# RMP_SLIDER_MODULE.net
KiCad netlist of a schematic drawn in Altium Designer
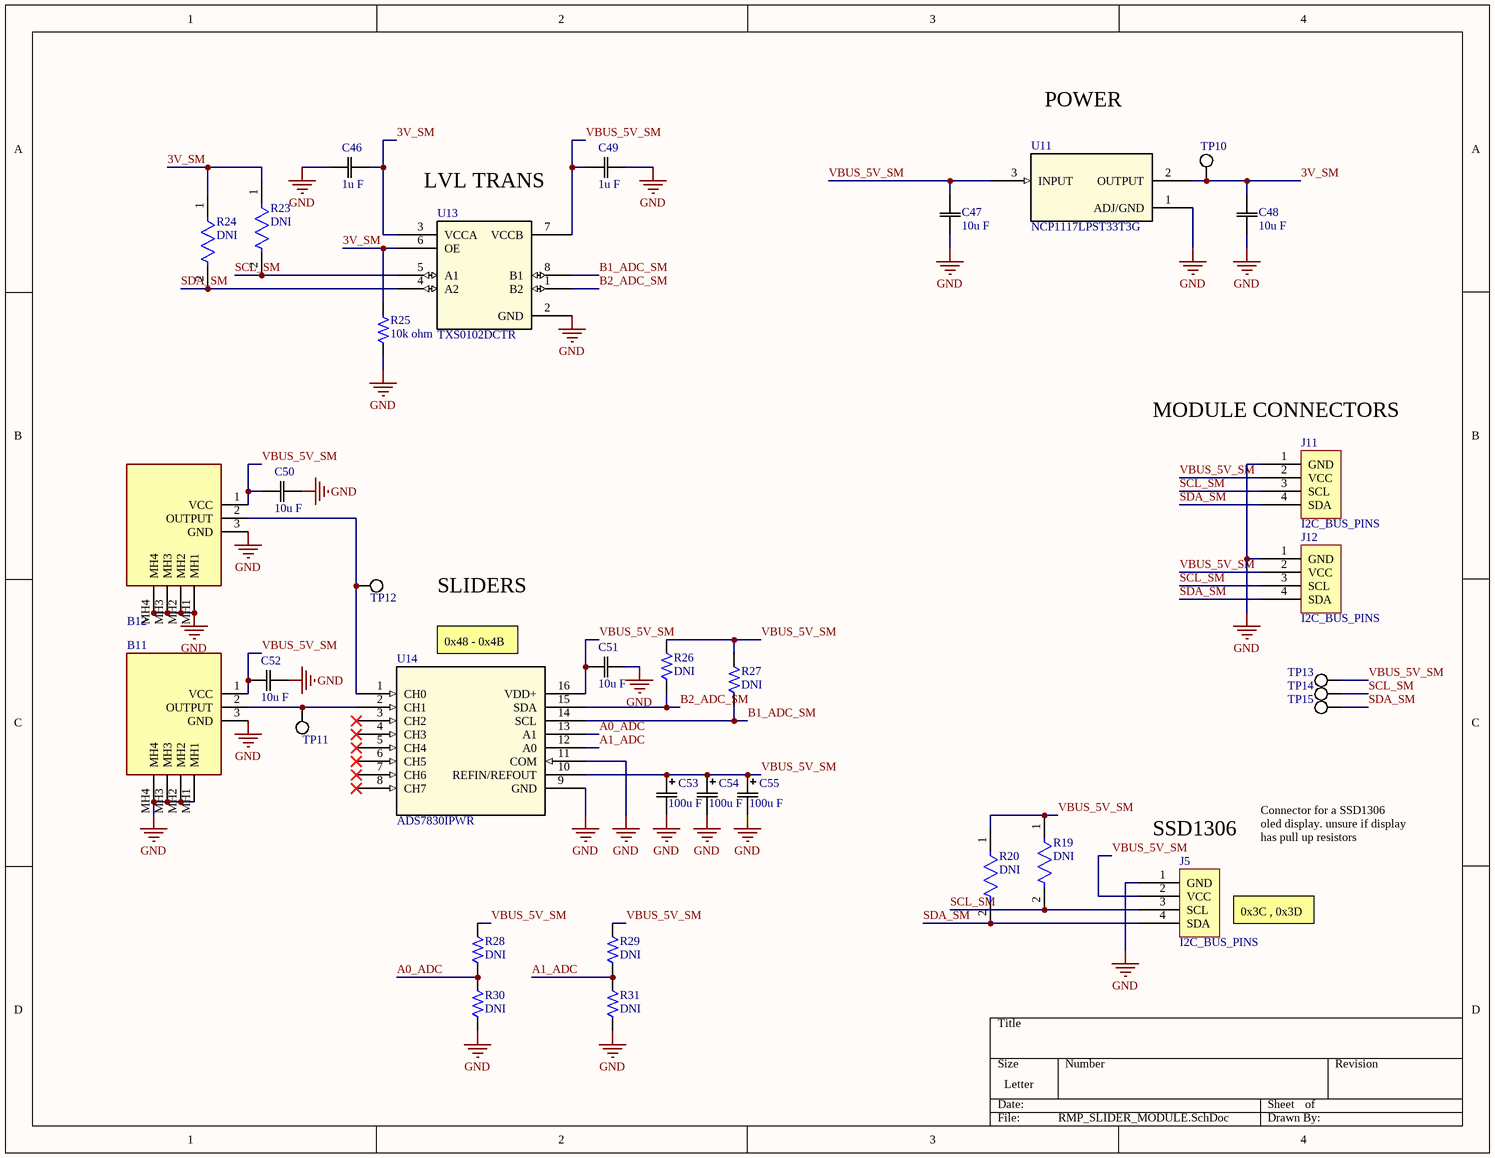
[diagram p0: RMP_SLIDER_MODULE.SchDoc]

(export (version "E")
  (design (tool "Eeschema 10.0.6"))
  (components
    (comp (ref "B11")
      (value "PTA3043-2010CIB103")
      (footprint "PTA30432010CIB103")
      (description "10 kOhms 0.2W, 1/5W Through Hole Slide Potentiometer Top Adjustment Type")
      (fields (field (name "MOUSER PART NUMBER") "652-PTA3432010CIB103"))
      (libsource (lib "Schlib1") (part "PTA3043-2010CIB103"))
    )
    (comp (ref "B12")
      (value "PTA3043-2010CIB103")
      (footprint "PTA30432010CIB103")
      (description "10 kOhms 0.2W, 1/5W Through Hole Slide Potentiometer Top Adjustment Type")
      (fields (field (name "MOUSER PART NUMBER") "652-PTA3432010CIB103"))
      (libsource (lib "Schlib1") (part "PTA3043-2010CIB103"))
    )
    (comp (ref "C46")
      (value "1u F")
      (footprint "CAP_CL21B105KAFNNNE_SAM-M")
      (description "1 µF ±10% 25V Ceramic Capacitor X7R 0805 (2012 Metric)")
      (fields (field (name "Comment") "CL21B105KAFNNNE"))
      (libsource (lib "Schlib1") (part "CAP_CL21B105KAFNNNE"))
    )
    (comp (ref "C47")
      (value "10u F")
      (footprint "G-21_MUR-M")
      (description "10 µF ±10% 16V Ceramic Capacitor X5R 0805 (2012 Metric)")
      (fields (field (name "Comment") "GRM21BR61C106KE15K"))
      (libsource (lib "Schlib1") (part "CAP_GRM21BR61C106KE15K"))
    )
    (comp (ref "C48")
      (value "10u F")
      (footprint "G-21_MUR-M")
      (description "10 µF ±10% 16V Ceramic Capacitor X5R 0805 (2012 Metric)")
      (fields (field (name "Comment") "GRM21BR61C106KE15K"))
      (libsource (lib "Schlib1") (part "CAP_GRM21BR61C106KE15K"))
    )
    (comp (ref "C49")
      (value "1u F")
      (footprint "CAP_CL21B105KAFNNNE_SAM-M")
      (description "1 µF ±10% 25V Ceramic Capacitor X7R 0805 (2012 Metric)")
      (fields (field (name "Comment") "CL21B105KAFNNNE"))
      (libsource (lib "Schlib1") (part "CAP_CL21B105KAFNNNE"))
    )
    (comp (ref "C50")
      (value "10u F")
      (footprint "G-21_MUR-M")
      (description "10 µF ±10% 16V Ceramic Capacitor X5R 0805 (2012 Metric)")
      (fields (field (name "Comment") "GRM21BR61C106KE15K"))
      (libsource (lib "Schlib1") (part "CAP_GRM21BR61C106KE15K"))
    )
    (comp (ref "C51")
      (value "10u F")
      (footprint "G-21_MUR-M")
      (description "10 µF ±10% 16V Ceramic Capacitor X5R 0805 (2012 Metric)")
      (fields (field (name "Comment") "GRM21BR61C106KE15K"))
      (libsource (lib "Schlib1") (part "CAP_GRM21BR61C106KE15K"))
    )
    (comp (ref "C52")
      (value "10u F")
      (footprint "G-21_MUR-M")
      (description "10 µF ±10% 16V Ceramic Capacitor X5R 0805 (2012 Metric)")
      (fields (field (name "Comment") "GRM21BR61C106KE15K"))
      (libsource (lib "Schlib1") (part "CAP_GRM21BR61C106KE15K"))
    )
    (comp (ref "C53")
      (value "100u F")
      (footprint "CAP_YX_6P3X11_RUB")
      (description "CAP ALUM 100UF 20% 35V RADIAL TH")
      (fields (field (name "Comment") "35YXJ100M6.3X11"))
      (libsource (lib "Schlib1") (part "CAP_35YXJ100M6.3X11"))
    )
    (comp (ref "C54")
      (value "100u F")
      (footprint "CAP_YX_6P3X11_RUB")
      (description "CAP ALUM 100UF 20% 35V RADIAL TH")
      (fields (field (name "Comment") "35YXJ100M6.3X11"))
      (libsource (lib "Schlib1") (part "CAP_35YXJ100M6.3X11"))
    )
    (comp (ref "C55")
      (value "100u F")
      (footprint "CAP_YX_6P3X11_RUB")
      (description "CAP ALUM 100UF 20% 35V RADIAL TH")
      (fields (field (name "Comment") "35YXJ100M6.3X11"))
      (libsource (lib "Schlib1") (part "CAP_35YXJ100M6.3X11"))
    )
    (comp (ref "J5")
      (value "I2C_BUS_PINS")
      (footprint "4 PIN HEADER")
      (libsource (lib "Schlib1") (part "I2C_BUS_PINS"))
    )
    (comp (ref "J11")
      (value "I2C_BUS_PINS")
      (footprint "4 PIN HEADER")
      (libsource (lib "Schlib1") (part "I2C_BUS_PINS"))
    )
    (comp (ref "J12")
      (value "I2C_BUS_PINS")
      (footprint "4 PIN HEADER")
      (libsource (lib "Schlib1") (part "I2C_BUS_PINS"))
    )
    (comp (ref "R19")
      (value "RT0805FRE134K7L")
      (footprint "FP-RT0805-MFG")
      (description "RT0805 4.7KΩ 0.125W 50 ppm/°C 0.01%")
      (fields
        (field (name "RESISTANCE") "DNI")
        (field (name "TOLERANCE") "0.0001")
        (field (name "MANUFACTURER") "Yageo")
      )
      (libsource (lib "Altium Content Vault") (part "1029c3af85768c4190bb7ad29bc67b5"))
    )
    (comp (ref "R20")
      (value "RT0805FRE134K7L")
      (footprint "FP-RT0805-MFG")
      (description "RT0805 4.7KΩ 0.125W 50 ppm/°C 0.01%")
      (fields
        (field (name "RESISTANCE") "DNI")
        (field (name "TOLERANCE") "0.0001")
        (field (name "MANUFACTURER") "Yageo")
      )
      (libsource (lib "Altium Content Vault") (part "1029c3af85768c4190bb7ad29bc67b5"))
    )
    (comp (ref "R23")
      (value "RT0805FRE134K7L")
      (footprint "FP-RT0805-MFG")
      (description "RT0805 4.7KΩ 0.125W 50 ppm/°C 0.01%")
      (fields
        (field (name "RESISTANCE") "DNI")
        (field (name "TOLERANCE") "0.0001")
        (field (name "MANUFACTURER") "Yageo")
      )
      (libsource (lib "Altium Content Vault") (part "1029c3af85768c4190bb7ad29bc67b5"))
    )
    (comp (ref "R24")
      (value "RT0805FRE134K7L")
      (footprint "FP-RT0805-MFG")
      (description "RT0805 4.7KΩ 0.125W 50 ppm/°C 0.01%")
      (fields
        (field (name "RESISTANCE") "DNI")
        (field (name "TOLERANCE") "0.0001")
        (field (name "MANUFACTURER") "Yageo")
      )
      (libsource (lib "Altium Content Vault") (part "1029c3af85768c4190bb7ad29bc67b5"))
    )
    (comp (ref "R25")
      (value "10k ohm")
      (footprint "STA_RNCP0805_STP-M")
      (description "10 kOhms ±1% 0.25W, 1/4W Chip Resistor 0805 (2012 Metric) Anti-Sulfur Thin Film")
      (fields (field (name "Comment") "RNCP0805FTD10K0"))
      (libsource (lib "Schlib1") (part "RES_RNCP0805FTD10K0"))
    )
    (comp (ref "R26")
      (value "DNI")
      (footprint "STA_RNCP0805_STP-M")
      (description "10 kOhms ±1% 0.25W, 1/4W Chip Resistor 0805 (2012 Metric) Anti-Sulfur Thin Film")
      (fields (field (name "Comment") "RNCP0805FTD10K0"))
      (libsource (lib "Schlib1") (part "RES_RNCP0805FTD10K0"))
    )
    (comp (ref "R27")
      (value "DNI")
      (footprint "STA_RNCP0805_STP-M")
      (description "10 kOhms ±1% 0.25W, 1/4W Chip Resistor 0805 (2012 Metric) Anti-Sulfur Thin Film")
      (fields (field (name "Comment") "RNCP0805FTD10K0"))
      (libsource (lib "Schlib1") (part "RES_RNCP0805FTD10K0"))
    )
    (comp (ref "R28")
      (value "DNI")
      (footprint "STA_RNCP0805_STP-M")
      (description "10 kOhms ±1% 0.25W, 1/4W Chip Resistor 0805 (2012 Metric) Anti-Sulfur Thin Film")
      (fields (field (name "Comment") "RNCP0805FTD10K0"))
      (libsource (lib "Schlib1") (part "RES_RNCP0805FTD10K0"))
    )
    (comp (ref "R29")
      (value "DNI")
      (footprint "STA_RNCP0805_STP-M")
      (description "10 kOhms ±1% 0.25W, 1/4W Chip Resistor 0805 (2012 Metric) Anti-Sulfur Thin Film")
      (fields (field (name "Comment") "RNCP0805FTD10K0"))
      (libsource (lib "Schlib1") (part "RES_RNCP0805FTD10K0"))
    )
    (comp (ref "R30")
      (value "DNI")
      (footprint "STA_RNCP0805_STP-M")
      (description "10 kOhms ±1% 0.25W, 1/4W Chip Resistor 0805 (2012 Metric) Anti-Sulfur Thin Film")
      (fields (field (name "Comment") "RNCP0805FTD10K0"))
      (libsource (lib "Schlib1") (part "RES_RNCP0805FTD10K0"))
    )
    (comp (ref "R31")
      (value "DNI")
      (footprint "STA_RNCP0805_STP-M")
      (description "10 kOhms ±1% 0.25W, 1/4W Chip Resistor 0805 (2012 Metric) Anti-Sulfur Thin Film")
      (fields (field (name "Comment") "RNCP0805FTD10K0"))
      (libsource (lib "Schlib1") (part "RES_RNCP0805FTD10K0"))
    )
    (comp (ref "TP10")
      (value "TestPoint")
      (footprint "Testpoint")
      (libsource (lib "Schlib1") (part "TestPoint"))
    )
    (comp (ref "TP11")
      (value "TestPoint")
      (footprint "Testpoint")
      (libsource (lib "Schlib1") (part "TestPoint"))
    )
    (comp (ref "TP12") (value "TestPoint") (footprint "Testpoint") (libsource (lib "") (part "TestPoint_1")))
    (comp (ref "TP13")
      (value "TestPoint")
      (footprint "Testpoint")
      (libsource (lib "Schlib1") (part "TestPoint"))
    )
    (comp (ref "TP14")
      (value "TestPoint")
      (footprint "Testpoint")
      (libsource (lib "Schlib1") (part "TestPoint"))
    )
    (comp (ref "TP15")
      (value "TestPoint")
      (footprint "Testpoint")
      (libsource (lib "Schlib1") (part "TestPoint"))
    )
    (comp (ref "U11")
      (value "NCP1117LPST33T3G")
      (footprint "SOT223-3_ONS-M")
      (description "Linear Voltage Regulator IC Positive Fixed 1 Output 1A SOT-223")
      (libsource (lib "Schlib1") (part "NCP1117LPST33T3G"))
    )
    (comp (ref "U13")
      (value "TXS0102DCTR")
      (footprint "DCT8")
      (description "Voltage Level Translator Bidirectional 1 Circuit 2 Channel 24Mbps SM8")
      (libsource (lib "Schlib1") (part "TXS0102DCTR"))
    )
    (comp (ref "U14")
      (value "ADS7830IPWR")
      (footprint "PW16-M")
      (description "8 Bit Analog to Digital Converter 4, 8 Input 1 SAR 16-TSSOP")
      (libsource (lib "Schlib1") (part "ADS7830IPWR"))
    )
  )
  (nets
    (net (code "1") (name "/3V_SM") (class "Default")
      (node (ref "C46") (pin "1") (pinfunction "1_1") (pintype "passive"))
      (node (ref "C48") (pin "2") (pinfunction "2_2") (pintype "passive"))
      (node (ref "R23") (pin "1") (pinfunction "1_1") (pintype "passive"))
      (node (ref "R24") (pin "1") (pinfunction "1_1") (pintype "passive"))
      (node (ref "R25") (pin "1") (pinfunction "1_1") (pintype "passive"))
      (node (ref "TP10") (pin "1") (pinfunction "1_1") (pintype "passive"))
      (node (ref "U11") (pin "2") (pinfunction "OUTPUT_2") (pintype "power_in"))
      (node (ref "U13") (pin "3") (pinfunction "VCCA_3") (pintype "power_in"))
      (node (ref "U13") (pin "6") (pinfunction "OE_6") (pintype "power_in"))
    )
    (net (code "2") (name "/A0_ADC") (class "Default")
      (node (ref "R28") (pin "1") (pinfunction "1_1") (pintype "passive"))
      (node (ref "R30") (pin "2") (pinfunction "2_2") (pintype "passive"))
      (node (ref "U14") (pin "13") (pinfunction "A1_13") (pintype "passive"))
    )
    (net (code "3") (name "/A1_ADC") (class "Default")
      (node (ref "R29") (pin "1") (pinfunction "1_1") (pintype "passive"))
      (node (ref "R31") (pin "2") (pinfunction "2_2") (pintype "passive"))
      (node (ref "U14") (pin "12") (pinfunction "A0_12") (pintype "passive"))
    )
    (net (code "4") (name "/B1_ADC_SM") (class "Default")
      (node (ref "R27") (pin "1") (pinfunction "1_1") (pintype "passive"))
      (node (ref "U13") (pin "8") (pinfunction "B1_8") (pintype "bidirectional"))
      (node (ref "U14") (pin "14") (pinfunction "SCL_14") (pintype "passive"))
    )
    (net (code "5") (name "/B2_ADC_SM") (class "Default")
      (node (ref "R26") (pin "1") (pinfunction "1_1") (pintype "passive"))
      (node (ref "U13") (pin "1") (pinfunction "B2_1") (pintype "bidirectional"))
      (node (ref "U14") (pin "15") (pinfunction "SDA_15") (pintype "passive"))
    )
    (net (code "6") (name "/SCL_SM") (class "Default")
      (node (ref "J11") (pin "3") (pinfunction "SCL_3") (pintype "passive"))
      (node (ref "J12") (pin "3") (pinfunction "SCL_3") (pintype "passive"))
      (node (ref "J5") (pin "3") (pinfunction "SCL_3") (pintype "passive"))
      (node (ref "R19") (pin "2") (pinfunction "2_2") (pintype "passive"))
      (node (ref "R23") (pin "2") (pinfunction "2_2") (pintype "passive"))
      (node (ref "TP14") (pin "1") (pinfunction "1_1") (pintype "passive"))
      (node (ref "U13") (pin "5") (pinfunction "A1_5") (pintype "bidirectional"))
    )
    (net (code "7") (name "/SDA_SM") (class "Default")
      (node (ref "J11") (pin "4") (pinfunction "SDA_4") (pintype "passive"))
      (node (ref "J12") (pin "4") (pinfunction "SDA_4") (pintype "passive"))
      (node (ref "J5") (pin "4") (pinfunction "SDA_4") (pintype "passive"))
      (node (ref "R20") (pin "2") (pinfunction "2_2") (pintype "passive"))
      (node (ref "R24") (pin "2") (pinfunction "2_2") (pintype "passive"))
      (node (ref "TP15") (pin "1") (pinfunction "1_1") (pintype "passive"))
      (node (ref "U13") (pin "4") (pinfunction "A2_4") (pintype "bidirectional"))
    )
    (net (code "8") (name "/VBUS_5V_SM") (class "Default")
      (node (ref "B11") (pin "1") (pinfunction "VCC_1") (pintype "passive"))
      (node (ref "B12") (pin "1") (pinfunction "VCC_1") (pintype "passive"))
      (node (ref "C47") (pin "2") (pinfunction "2_2") (pintype "passive"))
      (node (ref "C49") (pin "2") (pinfunction "2_2") (pintype "passive"))
      (node (ref "C50") (pin "2") (pinfunction "2_2") (pintype "passive"))
      (node (ref "C51") (pin "2") (pinfunction "2_2") (pintype "passive"))
      (node (ref "C52") (pin "1") (pinfunction "1_1") (pintype "passive"))
      (node (ref "C53") (pin "1") (pinfunction "1_1") (pintype "passive"))
      (node (ref "C54") (pin "1") (pinfunction "1_1") (pintype "passive"))
      (node (ref "C55") (pin "1") (pinfunction "1_1") (pintype "passive"))
      (node (ref "J11") (pin "2") (pinfunction "VCC_2") (pintype "passive"))
      (node (ref "J12") (pin "2") (pinfunction "VCC_2") (pintype "passive"))
      (node (ref "J5") (pin "2") (pinfunction "VCC_2") (pintype "passive"))
      (node (ref "R19") (pin "1") (pinfunction "1_1") (pintype "passive"))
      (node (ref "R20") (pin "1") (pinfunction "1_1") (pintype "passive"))
      (node (ref "R26") (pin "2") (pinfunction "2_2") (pintype "passive"))
      (node (ref "R27") (pin "2") (pinfunction "2_2") (pintype "passive"))
      (node (ref "R28") (pin "2") (pinfunction "2_2") (pintype "passive"))
      (node (ref "R29") (pin "2") (pinfunction "2_2") (pintype "passive"))
      (node (ref "TP13") (pin "1") (pinfunction "1_1") (pintype "passive"))
      (node (ref "U11") (pin "3") (pinfunction "INPUT_3") (pintype "input"))
      (node (ref "U13") (pin "7") (pinfunction "VCCB_7") (pintype "power_in"))
      (node (ref "U14") (pin "10") (pinfunction "REFIN/REFOUT_10") (pintype "power_in"))
      (node (ref "U14") (pin "16") (pinfunction "VDD+_16") (pintype "power_in"))
    )
    (net (code "9") (name "GND") (class "Default")
      (node (ref "B11") (pin "3") (pinfunction "GND_3") (pintype "passive"))
      (node (ref "B11") (pin "MH1") (pinfunction "MH1_MH1") (pintype "passive"))
      (node (ref "B11") (pin "MH2") (pinfunction "MH2_MH2") (pintype "passive"))
      (node (ref "B11") (pin "MH3") (pinfunction "MH3_MH3") (pintype "passive"))
      (node (ref "B11") (pin "MH4") (pinfunction "MH4_MH4") (pintype "passive"))
      (node (ref "B12") (pin "3") (pinfunction "GND_3") (pintype "passive"))
      (node (ref "B12") (pin "MH1") (pinfunction "MH1_MH1") (pintype "passive"))
      (node (ref "B12") (pin "MH2") (pinfunction "MH2_MH2") (pintype "passive"))
      (node (ref "B12") (pin "MH3") (pinfunction "MH3_MH3") (pintype "passive"))
      (node (ref "B12") (pin "MH4") (pinfunction "MH4_MH4") (pintype "passive"))
      (node (ref "C46") (pin "2") (pinfunction "2_2") (pintype "passive"))
      (node (ref "C47") (pin "1") (pinfunction "1_1") (pintype "passive"))
      (node (ref "C48") (pin "1") (pinfunction "1_1") (pintype "passive"))
      (node (ref "C49") (pin "1") (pinfunction "1_1") (pintype "passive"))
      (node (ref "C50") (pin "1") (pinfunction "1_1") (pintype "passive"))
      (node (ref "C51") (pin "1") (pinfunction "1_1") (pintype "passive"))
      (node (ref "C52") (pin "2") (pinfunction "2_2") (pintype "passive"))
      (node (ref "C53") (pin "2") (pinfunction "2_2") (pintype "passive"))
      (node (ref "C54") (pin "2") (pinfunction "2_2") (pintype "passive"))
      (node (ref "C55") (pin "2") (pinfunction "2_2") (pintype "passive"))
      (node (ref "J11") (pin "1") (pinfunction "GND_1") (pintype "passive"))
      (node (ref "J12") (pin "1") (pinfunction "GND_1") (pintype "passive"))
      (node (ref "J5") (pin "1") (pinfunction "GND_1") (pintype "passive"))
      (node (ref "R25") (pin "2") (pinfunction "2_2") (pintype "passive"))
      (node (ref "R30") (pin "1") (pinfunction "1_1") (pintype "passive"))
      (node (ref "R31") (pin "1") (pinfunction "1_1") (pintype "passive"))
      (node (ref "U11") (pin "1") (pinfunction "ADJ/GND_1") (pintype "power_in"))
      (node (ref "U13") (pin "2") (pinfunction "GND_2") (pintype "power_in"))
      (node (ref "U14") (pin "11") (pinfunction "COM_11") (pintype "input"))
      (node (ref "U14") (pin "9") (pinfunction "GND_9") (pintype "power_in"))
    )
    (net (code "10") (name "Net-(B11-OUTPUT)") (class "Default")
      (node (ref "B11") (pin "2") (pinfunction "OUTPUT_2") (pintype "passive"))
      (node (ref "TP11") (pin "1") (pinfunction "1_1") (pintype "passive"))
      (node (ref "U14") (pin "2") (pinfunction "CH1_2") (pintype "input"))
    )
    (net (code "11") (name "Net-(B12-OUTPUT)") (class "Default")
      (node (ref "B12") (pin "2") (pinfunction "OUTPUT_2") (pintype "passive"))
      (node (ref "TP12") (pin "1") (pinfunction "1_1") (pintype "passive"))
      (node (ref "U14") (pin "1") (pinfunction "CH0_1") (pintype "input"))
    )
    (net (code "12") (name "unconnected-(U14-CH2-Pad3)") (class "Default")
      (node (ref "U14") (pin "3") (pinfunction "CH2_3") (pintype "input+no_connect"))
    )
    (net (code "13") (name "unconnected-(U14-CH3-Pad4)") (class "Default")
      (node (ref "U14") (pin "4") (pinfunction "CH3_4") (pintype "input+no_connect"))
    )
    (net (code "14") (name "unconnected-(U14-CH4-Pad5)") (class "Default")
      (node (ref "U14") (pin "5") (pinfunction "CH4_5") (pintype "input+no_connect"))
    )
    (net (code "15") (name "unconnected-(U14-CH5-Pad6)") (class "Default")
      (node (ref "U14") (pin "6") (pinfunction "CH5_6") (pintype "input+no_connect"))
    )
    (net (code "16") (name "unconnected-(U14-CH6-Pad7)") (class "Default")
      (node (ref "U14") (pin "7") (pinfunction "CH6_7") (pintype "input+no_connect"))
    )
    (net (code "17") (name "unconnected-(U14-CH7-Pad8)") (class "Default")
      (node (ref "U14") (pin "8") (pinfunction "CH7_8") (pintype "input+no_connect"))
    )
  )
)
